# Secondary_Power.net
KiCad netlist of a schematic drawn in Altium Designer
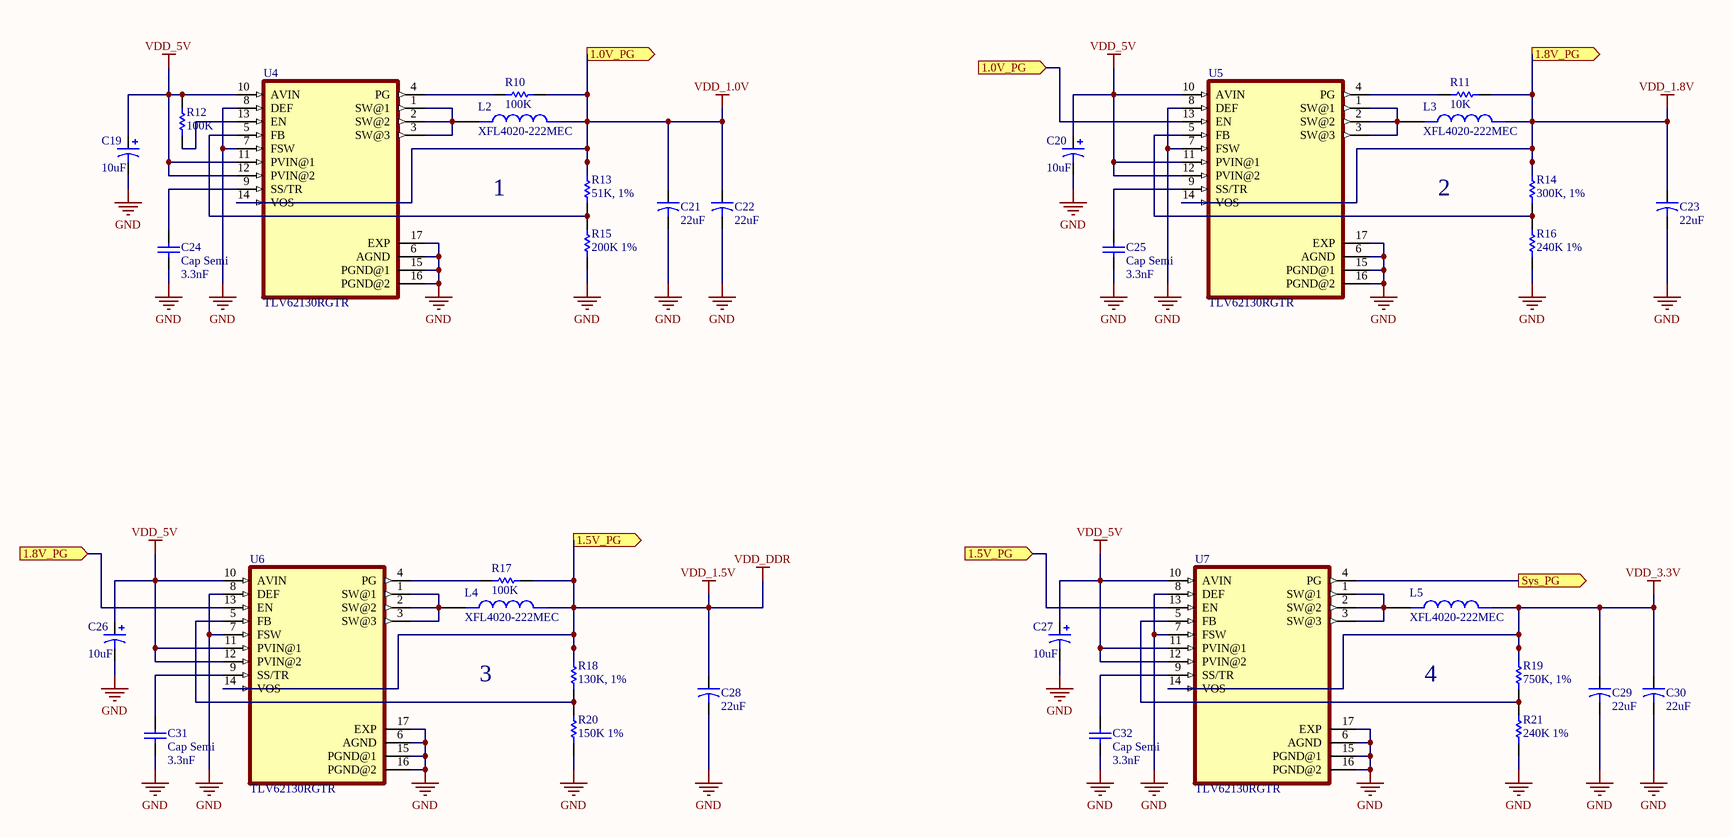
[diagram p0: Secondary_Power.SchDoc]

(export (version "E")
  (design (tool "Eeschema 10.0.6"))
  (components
    (comp (ref "C19")
      (value "10uF")
      (footprint "C0805")
      (description "Polarized Capacitor (Surface Mount)")
      (fields (field (name "Comment") "Pol3") (field (name "PUBLISHER") "Altium Limited"))
      (libsource (lib "Miscellaneous Devices") (part "Cap Pol3"))
    )
    (comp (ref "C20")
      (value "10uF")
      (footprint "C0805")
      (description "Polarized Capacitor (Surface Mount)")
      (fields (field (name "Comment") "Pol3") (field (name "PUBLISHER") "Altium Limited"))
      (libsource (lib "Miscellaneous Devices") (part "Cap Pol3"))
    )
    (comp (ref "C21")
      (value "22uF")
      (footprint "1206 COND")
      (description "Capacitor")
      (fields
        (field (name "MANUFACTURER") "Generic Components")
        (field (name "Comment") "756-040")
        (field (name "PUBLISHER") "Altium Limited")
      )
      (libsource (lib "lib_protel_HC") (part "Cap2_1"))
    )
    (comp (ref "C22")
      (value "22uF")
      (footprint "1206 COND")
      (description "Capacitor")
      (fields
        (field (name "MANUFACTURER") "Generic Components")
        (field (name "Comment") "756-040")
        (field (name "PUBLISHER") "Altium Limited")
      )
      (libsource (lib "lib_protel_HC") (part "Cap2_1"))
    )
    (comp (ref "C23")
      (value "22uF")
      (footprint "1206 COND")
      (description "Capacitor")
      (fields
        (field (name "MANUFACTURER") "Generic Components")
        (field (name "Comment") "756-040")
        (field (name "PUBLISHER") "Altium Limited")
      )
      (libsource (lib "lib_protel_HC") (part "Cap2_1"))
    )
    (comp (ref "C24")
      (value "Cap Semi")
      (footprint "1608[0603]")
      (description "Capacitor (Semiconductor SIM Model)")
      (fields (field (name "ALTIUM_VALUE") "3.3nF") (field (name "PUBLISHER") "Altium Limited"))
      (libsource (lib "Miscellaneous Devices") (part "Cap Semi"))
    )
    (comp (ref "C25")
      (value "Cap Semi")
      (footprint "1608[0603]")
      (description "Capacitor (Semiconductor SIM Model)")
      (fields (field (name "ALTIUM_VALUE") "3.3nF") (field (name "PUBLISHER") "Altium Limited"))
      (libsource (lib "Miscellaneous Devices") (part "Cap Semi"))
    )
    (comp (ref "C26")
      (value "10uF")
      (footprint "C0805")
      (description "Polarized Capacitor (Surface Mount)")
      (fields (field (name "Comment") "Pol3") (field (name "PUBLISHER") "Altium Limited"))
      (libsource (lib "Miscellaneous Devices") (part "Cap Pol3"))
    )
    (comp (ref "C27")
      (value "10uF")
      (footprint "C0805")
      (description "Polarized Capacitor (Surface Mount)")
      (fields (field (name "Comment") "Pol3") (field (name "PUBLISHER") "Altium Limited"))
      (libsource (lib "Miscellaneous Devices") (part "Cap Pol3"))
    )
    (comp (ref "C28")
      (value "22uF")
      (footprint "1206 COND")
      (description "Capacitor")
      (fields
        (field (name "MANUFACTURER") "Generic Components")
        (field (name "Comment") "756-040")
        (field (name "PUBLISHER") "Altium Limited")
      )
      (libsource (lib "lib_protel_HC") (part "Cap2_1"))
    )
    (comp (ref "C29")
      (value "22uF")
      (footprint "1206 COND")
      (description "Capacitor")
      (fields
        (field (name "MANUFACTURER") "Generic Components")
        (field (name "Comment") "756-040")
        (field (name "PUBLISHER") "Altium Limited")
      )
      (libsource (lib "lib_protel_HC") (part "Cap2_1"))
    )
    (comp (ref "C30")
      (value "22uF")
      (footprint "1206 COND")
      (description "Capacitor")
      (fields
        (field (name "MANUFACTURER") "Generic Components")
        (field (name "Comment") "756-040")
        (field (name "PUBLISHER") "Altium Limited")
      )
      (libsource (lib "lib_protel_HC") (part "Cap2_1"))
    )
    (comp (ref "C31")
      (value "Cap Semi")
      (footprint "1608[0603]")
      (description "Capacitor (Semiconductor SIM Model)")
      (fields (field (name "ALTIUM_VALUE") "3.3nF") (field (name "PUBLISHER") "Altium Limited"))
      (libsource (lib "Miscellaneous Devices") (part "Cap Semi"))
    )
    (comp (ref "C32")
      (value "Cap Semi")
      (footprint "1608[0603]")
      (description "Capacitor (Semiconductor SIM Model)")
      (fields (field (name "ALTIUM_VALUE") "3.3nF") (field (name "PUBLISHER") "Altium Limited"))
      (libsource (lib "Miscellaneous Devices") (part "Cap Semi"))
    )
    (comp (ref "L2")
      (value "XFL4020-222MEC")
      (footprint "IND_XFL4020-222MEC")
      (description "Power inductor, shielded, 20% tol, SMT, RoHS, halogen free")
      (fields (field (name "MF") "Coilcraft"))
      (libsource (lib "XFL4020-222MEC") (part "XFL4020-222MEC"))
    )
    (comp (ref "L3")
      (value "XFL4020-222MEC")
      (footprint "IND_XFL4020-222MEC")
      (description "Power inductor, shielded, 20% tol, SMT, RoHS, halogen free")
      (fields (field (name "MF") "Coilcraft"))
      (libsource (lib "XFL4020-222MEC") (part "XFL4020-222MEC"))
    )
    (comp (ref "L4")
      (value "XFL4020-222MEC")
      (footprint "IND_XFL4020-222MEC")
      (description "Power inductor, shielded, 20% tol, SMT, RoHS, halogen free")
      (fields (field (name "MF") "Coilcraft"))
      (libsource (lib "XFL4020-222MEC") (part "XFL4020-222MEC"))
    )
    (comp (ref "L5")
      (value "XFL4020-222MEC")
      (footprint "IND_XFL4020-222MEC")
      (description "Power inductor, shielded, 20% tol, SMT, RoHS, halogen free")
      (fields (field (name "MF") "Coilcraft"))
      (libsource (lib "XFL4020-222MEC") (part "XFL4020-222MEC"))
    )
    (comp (ref "R10")
      (value "100K")
      (footprint "0603")
      (description "Resistor")
      (fields
        (field (name "MANUFACTURER") "Generic Components")
        (field (name "Comment") "Res1")
        (field (name "PUBLISHER") "Altium Limited")
      )
      (libsource (lib "lib_protel_HC") (part "Res1_1"))
    )
    (comp (ref "R11")
      (value "10K")
      (footprint "0603")
      (description "Resistor")
      (fields
        (field (name "MANUFACTURER") "Generic Components")
        (field (name "Comment") "Res1")
        (field (name "PUBLISHER") "Altium Limited")
      )
      (libsource (lib "lib_protel_HC") (part "Res1_1"))
    )
    (comp (ref "R12")
      (value "100K")
      (footprint "0603")
      (description "Resistor")
      (fields
        (field (name "MANUFACTURER") "Generic Components")
        (field (name "Comment") "Res1")
        (field (name "PUBLISHER") "Altium Limited")
      )
      (libsource (lib "lib_protel_HC") (part "Res1_1"))
    )
    (comp (ref "R13")
      (value "51K, 1%")
      (footprint "0603")
      (description "Resistor")
      (fields
        (field (name "MANUFACTURER") "Generic Components")
        (field (name "Comment") "Res1")
        (field (name "PUBLISHER") "Altium Limited")
      )
      (libsource (lib "lib_protel_HC") (part "Res1_1"))
    )
    (comp (ref "R14")
      (value "300K, 1%")
      (footprint "0603")
      (description "Resistor")
      (fields
        (field (name "MANUFACTURER") "Generic Components")
        (field (name "Comment") "Res1")
        (field (name "PUBLISHER") "Altium Limited")
      )
      (libsource (lib "lib_protel_HC") (part "Res1_1"))
    )
    (comp (ref "R15")
      (value "200K 1%")
      (footprint "0603")
      (description "Resistor")
      (fields
        (field (name "MANUFACTURER") "Generic Components")
        (field (name "Comment") "Res1")
        (field (name "PUBLISHER") "Altium Limited")
      )
      (libsource (lib "lib_protel_HC") (part "Res1_1"))
    )
    (comp (ref "R16")
      (value "240K 1%")
      (footprint "0603")
      (description "Resistor")
      (fields
        (field (name "MANUFACTURER") "Generic Components")
        (field (name "Comment") "Res1")
        (field (name "PUBLISHER") "Altium Limited")
      )
      (libsource (lib "lib_protel_HC") (part "Res1_1"))
    )
    (comp (ref "R17")
      (value "100K")
      (footprint "0603")
      (description "Resistor")
      (fields
        (field (name "MANUFACTURER") "Generic Components")
        (field (name "Comment") "Res1")
        (field (name "PUBLISHER") "Altium Limited")
      )
      (libsource (lib "lib_protel_HC") (part "Res1_1"))
    )
    (comp (ref "R18")
      (value "130K, 1%")
      (footprint "0603")
      (description "Resistor")
      (fields
        (field (name "MANUFACTURER") "Generic Components")
        (field (name "Comment") "Res1")
        (field (name "PUBLISHER") "Altium Limited")
      )
      (libsource (lib "lib_protel_HC") (part "Res1_1"))
    )
    (comp (ref "R19")
      (value "750K, 1%")
      (footprint "0603")
      (description "Resistor")
      (fields
        (field (name "MANUFACTURER") "Generic Components")
        (field (name "Comment") "Res1")
        (field (name "PUBLISHER") "Altium Limited")
      )
      (libsource (lib "lib_protel_HC") (part "Res1_1"))
    )
    (comp (ref "R20")
      (value "150K 1%")
      (footprint "0603")
      (description "Resistor")
      (fields
        (field (name "MANUFACTURER") "Generic Components")
        (field (name "Comment") "Res1")
        (field (name "PUBLISHER") "Altium Limited")
      )
      (libsource (lib "lib_protel_HC") (part "Res1_1"))
    )
    (comp (ref "R21")
      (value "240K 1%")
      (footprint "0603")
      (description "Resistor")
      (fields
        (field (name "MANUFACTURER") "Generic Components")
        (field (name "Comment") "Res1")
        (field (name "PUBLISHER") "Altium Limited")
      )
      (libsource (lib "lib_protel_HC") (part "Res1_1"))
    )
    (comp (ref "U4")
      (value "TLV62130RGTR")
      (footprint "QFN50P300X300X100-17N")
      (description "3-17V 3A Step-Down Converter in 3x3 QFN Package 16-VQFN -40 to 85")
      (fields (field (name "MF") "Texas Instruments"))
      (libsource (lib "TLV62130RGTR") (part "TLV62130RGTR"))
    )
    (comp (ref "U5")
      (value "TLV62130RGTR")
      (footprint "QFN50P300X300X100-17N")
      (description "3-17V 3A Step-Down Converter in 3x3 QFN Package 16-VQFN -40 to 85")
      (fields (field (name "MF") "Texas Instruments"))
      (libsource (lib "TLV62130RGTR") (part "TLV62130RGTR"))
    )
    (comp (ref "U6")
      (value "TLV62130RGTR")
      (footprint "QFN50P300X300X100-17N")
      (description "3-17V 3A Step-Down Converter in 3x3 QFN Package 16-VQFN -40 to 85")
      (fields (field (name "MF") "Texas Instruments"))
      (libsource (lib "TLV62130RGTR") (part "TLV62130RGTR"))
    )
    (comp (ref "U7")
      (value "TLV62130RGTR")
      (footprint "QFN50P300X300X100-17N")
      (description "3-17V 3A Step-Down Converter in 3x3 QFN Package 16-VQFN -40 to 85")
      (fields (field (name "MF") "Texas Instruments"))
      (libsource (lib "TLV62130RGTR") (part "TLV62130RGTR"))
    )
  )
  (nets
    (net (code "1") (name "/Sys_PG") (class "Default")
      (node (ref "U7") (pin "4") (pinfunction "PG_4") (pintype "output"))
    )
    (net (code "2") (name "GND") (class "Default")
      (node (ref "C19") (pin "2") (pinfunction "2_2") (pintype "passive"))
      (node (ref "C20") (pin "2") (pinfunction "2_2") (pintype "passive"))
      (node (ref "C21") (pin "1") (pinfunction "1_1") (pintype "passive"))
      (node (ref "C22") (pin "1") (pinfunction "1_1") (pintype "passive"))
      (node (ref "C23") (pin "1") (pinfunction "1_1") (pintype "passive"))
      (node (ref "C24") (pin "1") (pinfunction "1_1") (pintype "passive"))
      (node (ref "C25") (pin "1") (pinfunction "1_1") (pintype "passive"))
      (node (ref "C26") (pin "2") (pinfunction "2_2") (pintype "passive"))
      (node (ref "C27") (pin "2") (pinfunction "2_2") (pintype "passive"))
      (node (ref "C28") (pin "1") (pinfunction "1_1") (pintype "passive"))
      (node (ref "C29") (pin "1") (pinfunction "1_1") (pintype "passive"))
      (node (ref "C30") (pin "1") (pinfunction "1_1") (pintype "passive"))
      (node (ref "C31") (pin "1") (pinfunction "1_1") (pintype "passive"))
      (node (ref "C32") (pin "1") (pinfunction "1_1") (pintype "passive"))
      (node (ref "R15") (pin "2") (pinfunction "2_2") (pintype "passive"))
      (node (ref "R16") (pin "2") (pinfunction "2_2") (pintype "passive"))
      (node (ref "R20") (pin "2") (pinfunction "2_2") (pintype "passive"))
      (node (ref "R21") (pin "2") (pinfunction "2_2") (pintype "passive"))
      (node (ref "U4") (pin "15") (pinfunction "PGND@1_15") (pintype "power_in"))
      (node (ref "U4") (pin "16") (pinfunction "PGND@2_16") (pintype "power_in"))
      (node (ref "U4") (pin "17") (pinfunction "EXP_17") (pintype "power_in"))
      (node (ref "U4") (pin "6") (pinfunction "AGND_6") (pintype "power_in"))
      (node (ref "U4") (pin "7") (pinfunction "FSW_7") (pintype "input"))
      (node (ref "U4") (pin "8") (pinfunction "DEF_8") (pintype "input"))
      (node (ref "U5") (pin "15") (pinfunction "PGND@1_15") (pintype "power_in"))
      (node (ref "U5") (pin "16") (pinfunction "PGND@2_16") (pintype "power_in"))
      (node (ref "U5") (pin "17") (pinfunction "EXP_17") (pintype "power_in"))
      (node (ref "U5") (pin "6") (pinfunction "AGND_6") (pintype "power_in"))
      (node (ref "U5") (pin "7") (pinfunction "FSW_7") (pintype "input"))
      (node (ref "U5") (pin "8") (pinfunction "DEF_8") (pintype "input"))
      (node (ref "U6") (pin "15") (pinfunction "PGND@1_15") (pintype "power_in"))
      (node (ref "U6") (pin "16") (pinfunction "PGND@2_16") (pintype "power_in"))
      (node (ref "U6") (pin "17") (pinfunction "EXP_17") (pintype "power_in"))
      (node (ref "U6") (pin "6") (pinfunction "AGND_6") (pintype "power_in"))
      (node (ref "U6") (pin "7") (pinfunction "FSW_7") (pintype "input"))
      (node (ref "U6") (pin "8") (pinfunction "DEF_8") (pintype "input"))
      (node (ref "U7") (pin "15") (pinfunction "PGND@1_15") (pintype "power_in"))
      (node (ref "U7") (pin "16") (pinfunction "PGND@2_16") (pintype "power_in"))
      (node (ref "U7") (pin "17") (pinfunction "EXP_17") (pintype "power_in"))
      (node (ref "U7") (pin "6") (pinfunction "AGND_6") (pintype "power_in"))
      (node (ref "U7") (pin "7") (pinfunction "FSW_7") (pintype "input"))
      (node (ref "U7") (pin "8") (pinfunction "DEF_8") (pintype "input"))
    )
    (net (code "3") (name "Net-(U4-EN)") (class "Default")
      (node (ref "R12") (pin "2") (pinfunction "2_2") (pintype "passive"))
      (node (ref "U4") (pin "13") (pinfunction "EN_13") (pintype "input"))
    )
    (net (code "4") (name "Net-(U4-FB)") (class "Default")
      (node (ref "R13") (pin "2") (pinfunction "2_2") (pintype "passive"))
      (node (ref "R15") (pin "1") (pinfunction "1_1") (pintype "passive"))
      (node (ref "U4") (pin "5") (pinfunction "FB_5") (pintype "input"))
    )
    (net (code "5") (name "Net-(U4-PG)") (class "Default")
      (node (ref "R10") (pin "2") (pinfunction "2_2") (pintype "passive"))
      (node (ref "U4") (pin "4") (pinfunction "PG_4") (pintype "output"))
    )
    (net (code "6") (name "Net-(U4-SS{slash}TR)") (class "Default")
      (node (ref "C24") (pin "2") (pinfunction "2_2") (pintype "passive"))
      (node (ref "U4") (pin "9") (pinfunction "SS/TR_9") (pintype "input"))
    )
    (net (code "7") (name "Net-(U4-SW@1)") (class "Default")
      (node (ref "L2") (pin "1") (pinfunction "1_1") (pintype "passive"))
      (node (ref "U4") (pin "1") (pinfunction "SW@1_1") (pintype "output"))
      (node (ref "U4") (pin "2") (pinfunction "SW@2_2") (pintype "output"))
      (node (ref "U4") (pin "3") (pinfunction "SW@3_3") (pintype "output"))
    )
    (net (code "8") (name "Net-(U5-FB)") (class "Default")
      (node (ref "R14") (pin "2") (pinfunction "2_2") (pintype "passive"))
      (node (ref "R16") (pin "1") (pinfunction "1_1") (pintype "passive"))
      (node (ref "U5") (pin "5") (pinfunction "FB_5") (pintype "input"))
    )
    (net (code "9") (name "Net-(U5-PG)") (class "Default")
      (node (ref "R11") (pin "2") (pinfunction "2_2") (pintype "passive"))
      (node (ref "U5") (pin "4") (pinfunction "PG_4") (pintype "output"))
    )
    (net (code "10") (name "Net-(U5-SS{slash}TR)") (class "Default")
      (node (ref "C25") (pin "2") (pinfunction "2_2") (pintype "passive"))
      (node (ref "U5") (pin "9") (pinfunction "SS/TR_9") (pintype "input"))
    )
    (net (code "11") (name "Net-(U5-SW@1)") (class "Default")
      (node (ref "L3") (pin "1") (pinfunction "1_1") (pintype "passive"))
      (node (ref "U5") (pin "1") (pinfunction "SW@1_1") (pintype "output"))
      (node (ref "U5") (pin "2") (pinfunction "SW@2_2") (pintype "output"))
      (node (ref "U5") (pin "3") (pinfunction "SW@3_3") (pintype "output"))
    )
    (net (code "12") (name "Net-(U6-FB)") (class "Default")
      (node (ref "R18") (pin "2") (pinfunction "2_2") (pintype "passive"))
      (node (ref "R20") (pin "1") (pinfunction "1_1") (pintype "passive"))
      (node (ref "U6") (pin "5") (pinfunction "FB_5") (pintype "input"))
    )
    (net (code "13") (name "Net-(U6-PG)") (class "Default")
      (node (ref "R17") (pin "2") (pinfunction "2_2") (pintype "passive"))
      (node (ref "U6") (pin "4") (pinfunction "PG_4") (pintype "output"))
    )
    (net (code "14") (name "Net-(U6-SS{slash}TR)") (class "Default")
      (node (ref "C31") (pin "2") (pinfunction "2_2") (pintype "passive"))
      (node (ref "U6") (pin "9") (pinfunction "SS/TR_9") (pintype "input"))
    )
    (net (code "15") (name "Net-(U6-SW@1)") (class "Default")
      (node (ref "L4") (pin "1") (pinfunction "1_1") (pintype "passive"))
      (node (ref "U6") (pin "1") (pinfunction "SW@1_1") (pintype "output"))
      (node (ref "U6") (pin "2") (pinfunction "SW@2_2") (pintype "output"))
      (node (ref "U6") (pin "3") (pinfunction "SW@3_3") (pintype "output"))
    )
    (net (code "16") (name "Net-(U7-FB)") (class "Default")
      (node (ref "R19") (pin "2") (pinfunction "2_2") (pintype "passive"))
      (node (ref "R21") (pin "1") (pinfunction "1_1") (pintype "passive"))
      (node (ref "U7") (pin "5") (pinfunction "FB_5") (pintype "input"))
    )
    (net (code "17") (name "Net-(U7-SS{slash}TR)") (class "Default")
      (node (ref "C32") (pin "2") (pinfunction "2_2") (pintype "passive"))
      (node (ref "U7") (pin "9") (pinfunction "SS/TR_9") (pintype "input"))
    )
    (net (code "18") (name "Net-(U7-SW@1)") (class "Default")
      (node (ref "L5") (pin "1") (pinfunction "1_1") (pintype "passive"))
      (node (ref "U7") (pin "1") (pinfunction "SW@1_1") (pintype "output"))
      (node (ref "U7") (pin "2") (pinfunction "SW@2_2") (pintype "output"))
      (node (ref "U7") (pin "3") (pinfunction "SW@3_3") (pintype "output"))
    )
    (net (code "19") (name "VDD_1.0V") (class "Default")
      (node (ref "C21") (pin "2") (pinfunction "2_2") (pintype "passive"))
      (node (ref "C22") (pin "2") (pinfunction "2_2") (pintype "passive"))
      (node (ref "L2") (pin "2") (pinfunction "2_2") (pintype "passive"))
      (node (ref "R10") (pin "1") (pinfunction "1_1") (pintype "passive"))
      (node (ref "R13") (pin "1") (pinfunction "1_1") (pintype "passive"))
      (node (ref "U4") (pin "14") (pinfunction "VOS_14") (pintype "input"))
      (node (ref "U5") (pin "13") (pinfunction "EN_13") (pintype "input"))
    )
    (net (code "20") (name "VDD_1.5V") (class "Default")
      (node (ref "C28") (pin "2") (pinfunction "2_2") (pintype "passive"))
      (node (ref "L4") (pin "2") (pinfunction "2_2") (pintype "passive"))
      (node (ref "R17") (pin "1") (pinfunction "1_1") (pintype "passive"))
      (node (ref "R18") (pin "1") (pinfunction "1_1") (pintype "passive"))
      (node (ref "U6") (pin "14") (pinfunction "VOS_14") (pintype "input"))
      (node (ref "U7") (pin "13") (pinfunction "EN_13") (pintype "input"))
    )
    (net (code "21") (name "VDD_1.8V") (class "Default")
      (node (ref "C23") (pin "2") (pinfunction "2_2") (pintype "passive"))
      (node (ref "L3") (pin "2") (pinfunction "2_2") (pintype "passive"))
      (node (ref "R11") (pin "1") (pinfunction "1_1") (pintype "passive"))
      (node (ref "R14") (pin "1") (pinfunction "1_1") (pintype "passive"))
      (node (ref "U5") (pin "14") (pinfunction "VOS_14") (pintype "input"))
      (node (ref "U6") (pin "13") (pinfunction "EN_13") (pintype "input"))
    )
    (net (code "22") (name "VDD_3.3V") (class "Default")
      (node (ref "C29") (pin "2") (pinfunction "2_2") (pintype "passive"))
      (node (ref "C30") (pin "2") (pinfunction "2_2") (pintype "passive"))
      (node (ref "L5") (pin "2") (pinfunction "2_2") (pintype "passive"))
      (node (ref "R19") (pin "1") (pinfunction "1_1") (pintype "passive"))
      (node (ref "U7") (pin "14") (pinfunction "VOS_14") (pintype "input"))
    )
    (net (code "23") (name "VDD_5V") (class "Default")
      (node (ref "C19") (pin "1") (pinfunction "1_1") (pintype "passive"))
      (node (ref "C20") (pin "1") (pinfunction "1_1") (pintype "passive"))
      (node (ref "C26") (pin "1") (pinfunction "1_1") (pintype "passive"))
      (node (ref "C27") (pin "1") (pinfunction "1_1") (pintype "passive"))
      (node (ref "R12") (pin "1") (pinfunction "1_1") (pintype "passive"))
      (node (ref "U4") (pin "10") (pinfunction "AVIN_10") (pintype "input"))
      (node (ref "U4") (pin "11") (pinfunction "PVIN@1_11") (pintype "input"))
      (node (ref "U4") (pin "12") (pinfunction "PVIN@2_12") (pintype "input"))
      (node (ref "U5") (pin "10") (pinfunction "AVIN_10") (pintype "input"))
      (node (ref "U5") (pin "11") (pinfunction "PVIN@1_11") (pintype "input"))
      (node (ref "U5") (pin "12") (pinfunction "PVIN@2_12") (pintype "input"))
      (node (ref "U6") (pin "10") (pinfunction "AVIN_10") (pintype "input"))
      (node (ref "U6") (pin "11") (pinfunction "PVIN@1_11") (pintype "input"))
      (node (ref "U6") (pin "12") (pinfunction "PVIN@2_12") (pintype "input"))
      (node (ref "U7") (pin "10") (pinfunction "AVIN_10") (pintype "input"))
      (node (ref "U7") (pin "11") (pinfunction "PVIN@1_11") (pintype "input"))
      (node (ref "U7") (pin "12") (pinfunction "PVIN@2_12") (pintype "input"))
    )
  )
)
